# legoCrawlerArduinoMegaExtension.net
KiCad netlist of a schematic drawn in EAGLE
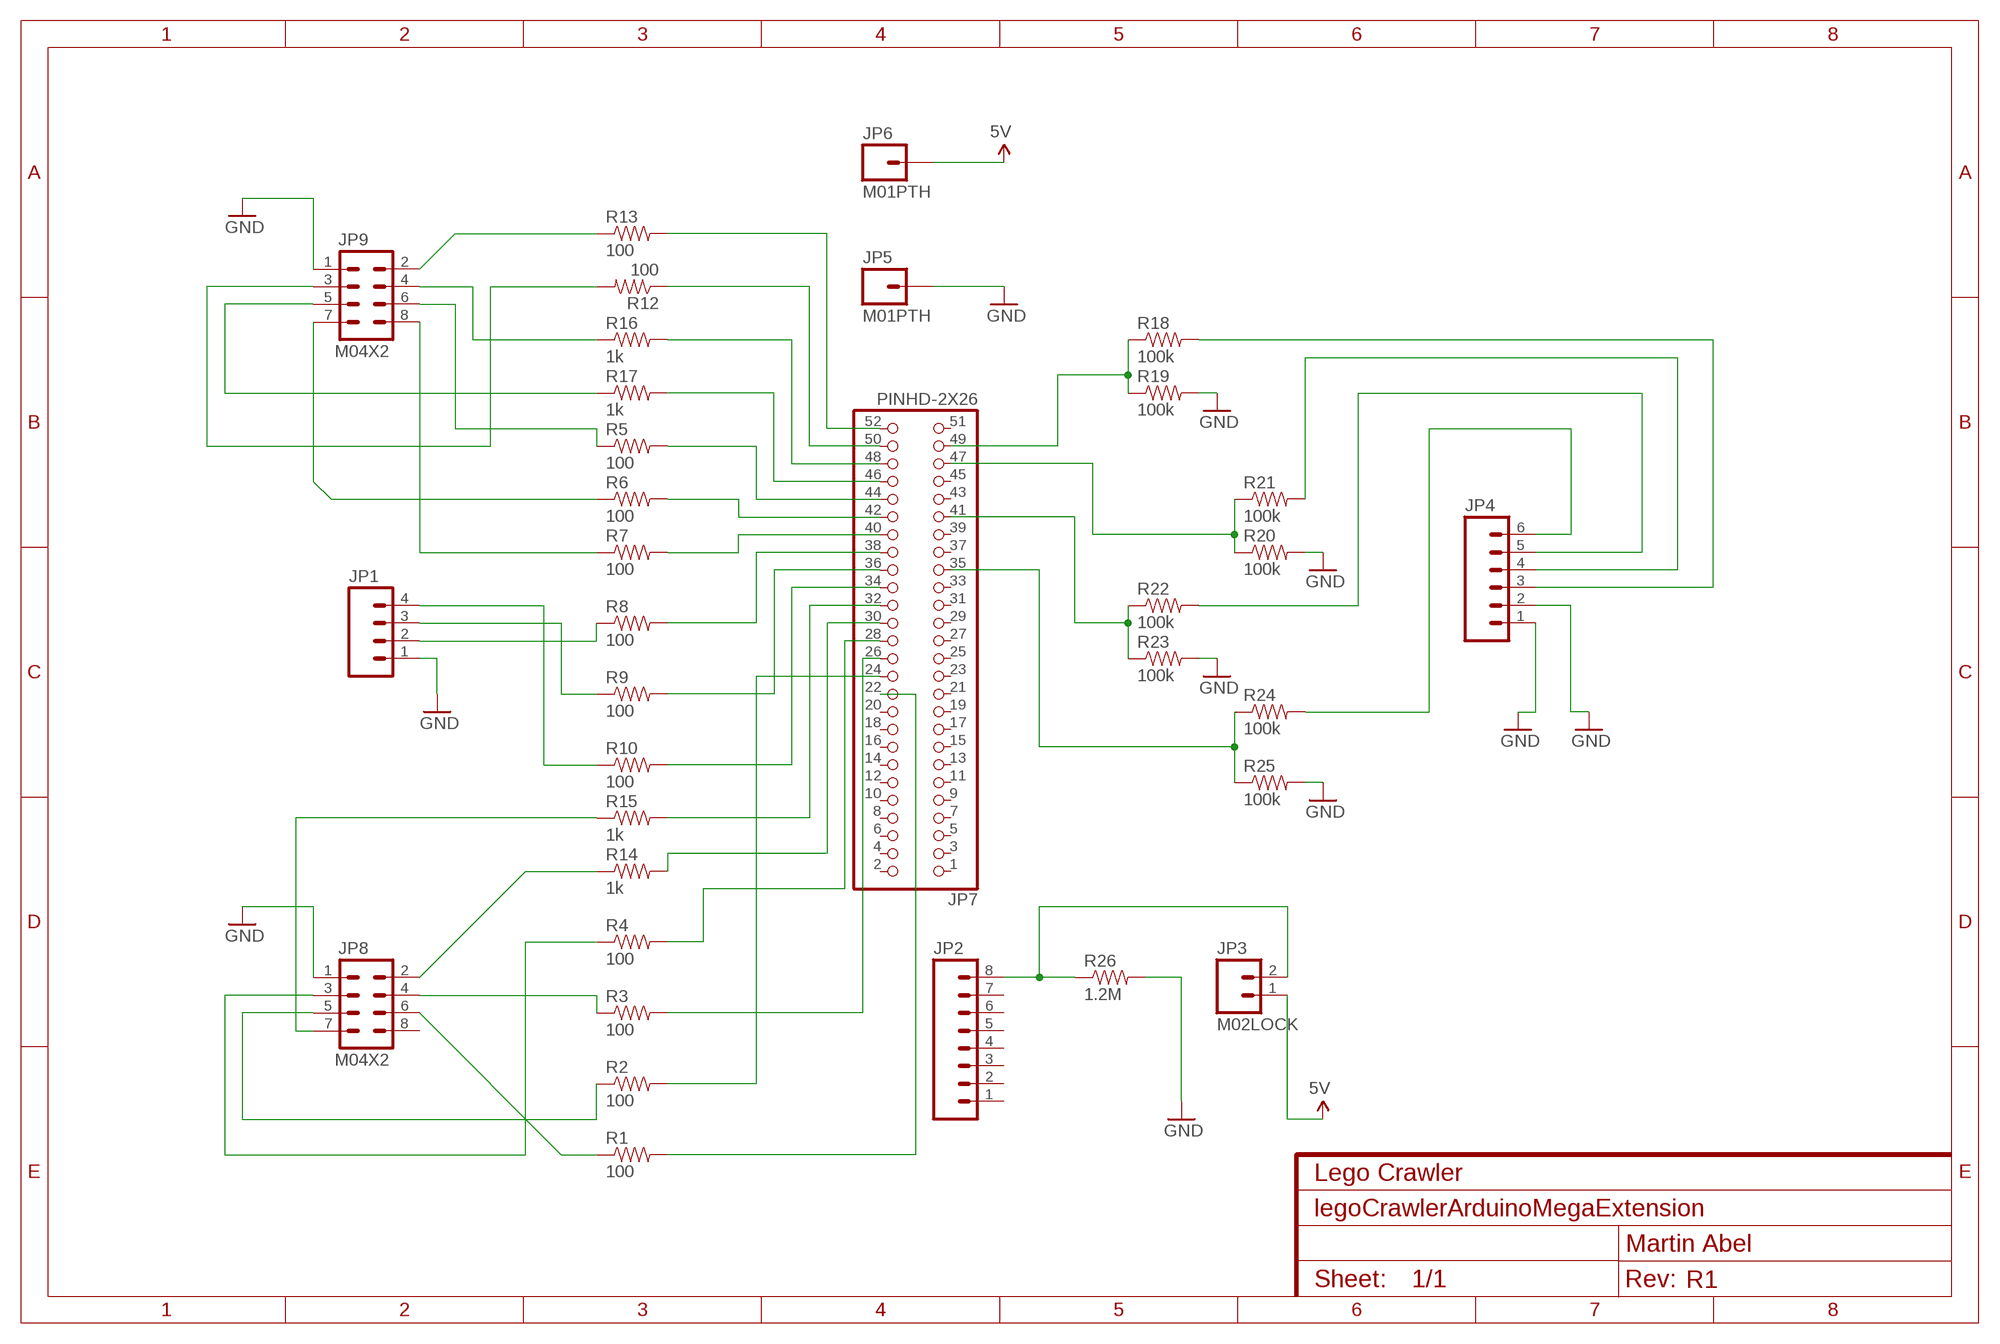
[diagram p0: schematic, sheet 1]

(export (version "E")
  (design (tool "Eeschema 10.0.6"))
  (components
    (comp (ref "JP1")
      (value "M04JST")
      (footprint "eagle-import:1X04-1.5MM_JST")
      (libsource (lib "eagle-import") (part "M04JST"))
    )
    (comp (ref "JP2")
      (value "M08")
      (footprint "eagle-import:1X08_ROUND")
      (libsource (lib "eagle-import") (part "M08"))
    )
    (comp (ref "JP3")
      (value "M02LOCK")
      (footprint "eagle-import:1X02_LOCK")
      (libsource (lib "eagle-import") (part "M02LOCK"))
    )
    (comp (ref "JP4")
      (value "M06LOCK")
      (footprint "eagle-import:1X06_LOCK")
      (libsource (lib "eagle-import") (part "M06LOCK"))
    )
    (comp (ref "JP5")
      (value "M01PTH")
      (footprint "eagle-import:1X01")
      (libsource (lib "eagle-import") (part "M01PTH"))
    )
    (comp (ref "JP6")
      (value "M01PTH")
      (footprint "eagle-import:1X01")
      (libsource (lib "eagle-import") (part "M01PTH"))
    )
    (comp (ref "JP7")
      (value "PINHD-2X26")
      (footprint "eagle-import:2X26")
      (libsource (lib "eagle-import") (part "PINHD-2X26"))
    )
    (comp (ref "JP8")
      (value "M04X2")
      (footprint "eagle-import:2X4")
      (libsource (lib "eagle-import") (part "M04X2"))
    )
    (comp (ref "JP9")
      (value "M04X2")
      (footprint "eagle-import:2X4")
      (libsource (lib "eagle-import") (part "M04X2"))
    )
    (comp (ref "R1")
      (value "100")
      (footprint "eagle-import:AXIAL-0.3")
      (libsource (lib "eagle-import") (part "10OHM-1/4W-5%(PTH)"))
    )
    (comp (ref "R2")
      (value "100")
      (footprint "eagle-import:AXIAL-0.3")
      (libsource (lib "eagle-import") (part "10OHM-1/4W-5%(PTH)"))
    )
    (comp (ref "R3")
      (value "100")
      (footprint "eagle-import:AXIAL-0.3")
      (libsource (lib "eagle-import") (part "10OHM-1/4W-5%(PTH)"))
    )
    (comp (ref "R4")
      (value "100")
      (footprint "eagle-import:AXIAL-0.3")
      (libsource (lib "eagle-import") (part "10OHM-1/4W-5%(PTH)"))
    )
    (comp (ref "R5")
      (value "100")
      (footprint "eagle-import:AXIAL-0.3")
      (libsource (lib "eagle-import") (part "10OHM-1/4W-5%(PTH)"))
    )
    (comp (ref "R6")
      (value "100")
      (footprint "eagle-import:AXIAL-0.3")
      (libsource (lib "eagle-import") (part "10OHM-1/4W-5%(PTH)"))
    )
    (comp (ref "R7")
      (value "100")
      (footprint "eagle-import:AXIAL-0.3")
      (libsource (lib "eagle-import") (part "10OHM-1/4W-5%(PTH)"))
    )
    (comp (ref "R8")
      (value "100")
      (footprint "eagle-import:AXIAL-0.3")
      (libsource (lib "eagle-import") (part "10OHM-1/4W-5%(PTH)"))
    )
    (comp (ref "R9")
      (value "100")
      (footprint "eagle-import:AXIAL-0.3")
      (libsource (lib "eagle-import") (part "10OHM-1/4W-5%(PTH)"))
    )
    (comp (ref "R10")
      (value "100")
      (footprint "eagle-import:AXIAL-0.3")
      (libsource (lib "eagle-import") (part "10OHM-1/4W-5%(PTH)"))
    )
    (comp (ref "R12")
      (value "100")
      (footprint "eagle-import:AXIAL-0.3")
      (libsource (lib "eagle-import") (part "10OHM-1/4W-5%(PTH)"))
    )
    (comp (ref "R13")
      (value "100")
      (footprint "eagle-import:AXIAL-0.3")
      (libsource (lib "eagle-import") (part "10OHM-1/4W-5%(PTH)"))
    )
    (comp (ref "R14")
      (value "1k")
      (footprint "eagle-import:AXIAL-0.3")
      (libsource (lib "eagle-import") (part "1KOHM-1/4W-5%(PTH)"))
    )
    (comp (ref "R15")
      (value "1k")
      (footprint "eagle-import:AXIAL-0.3")
      (libsource (lib "eagle-import") (part "1KOHM-1/4W-5%(PTH)"))
    )
    (comp (ref "R16")
      (value "1k")
      (footprint "eagle-import:AXIAL-0.3")
      (libsource (lib "eagle-import") (part "1KOHM-1/4W-5%(PTH)"))
    )
    (comp (ref "R17")
      (value "1k")
      (footprint "eagle-import:AXIAL-0.3")
      (libsource (lib "eagle-import") (part "1KOHM-1/4W-5%(PTH)"))
    )
    (comp (ref "R18")
      (value "100k")
      (footprint "eagle-import:AXIAL-0.3")
      (libsource (lib "eagle-import") (part "100KOHM-1/4W-5%(PTH)"))
    )
    (comp (ref "R19")
      (value "100k")
      (footprint "eagle-import:AXIAL-0.3")
      (libsource (lib "eagle-import") (part "100KOHM-1/4W-5%(PTH)"))
    )
    (comp (ref "R20")
      (value "100k")
      (footprint "eagle-import:AXIAL-0.3")
      (libsource (lib "eagle-import") (part "100KOHM-1/4W-5%(PTH)"))
    )
    (comp (ref "R21")
      (value "100k")
      (footprint "eagle-import:AXIAL-0.3")
      (libsource (lib "eagle-import") (part "100KOHM-1/4W-5%(PTH)"))
    )
    (comp (ref "R22")
      (value "100k")
      (footprint "eagle-import:AXIAL-0.3")
      (libsource (lib "eagle-import") (part "100KOHM-1/4W-5%(PTH)"))
    )
    (comp (ref "R23")
      (value "100k")
      (footprint "eagle-import:AXIAL-0.3")
      (libsource (lib "eagle-import") (part "100KOHM-1/4W-5%(PTH)"))
    )
    (comp (ref "R24")
      (value "100k")
      (footprint "eagle-import:AXIAL-0.3")
      (libsource (lib "eagle-import") (part "100KOHM-1/4W-5%(PTH)"))
    )
    (comp (ref "R25")
      (value "100k")
      (footprint "eagle-import:AXIAL-0.3")
      (libsource (lib "eagle-import") (part "100KOHM-1/4W-5%(PTH)"))
    )
    (comp (ref "R26")
      (value "1.2M")
      (footprint "eagle-import:0603-RES")
      (libsource (lib "eagle-import") (part "1.2MOHMS-1/10W-1%(0603)"))
    )
  )
  (nets
    (net (code "1") (name "5V") (class "Default")
      (node (ref "JP3") (pin "1") (pinfunction "1_1") (pintype "passive"))
      (node (ref "JP6") (pin "1") (pinfunction "1_1") (pintype "passive"))
    )
    (net (code "2") (name "GND") (class "Default")
      (node (ref "JP1") (pin "1") (pinfunction "1_1") (pintype "passive"))
      (node (ref "JP4") (pin "1") (pinfunction "1_1") (pintype "passive"))
      (node (ref "JP4") (pin "2") (pinfunction "2_2") (pintype "passive"))
      (node (ref "JP5") (pin "1") (pinfunction "1_1") (pintype "passive"))
      (node (ref "JP8") (pin "1") (pinfunction "1_1") (pintype "passive"))
      (node (ref "JP9") (pin "1") (pinfunction "1_1") (pintype "passive"))
      (node (ref "R19") (pin "P$2") (pinfunction "2_P$2") (pintype "passive"))
      (node (ref "R20") (pin "P$2") (pinfunction "2_P$2") (pintype "passive"))
      (node (ref "R23") (pin "P$2") (pinfunction "2_P$2") (pintype "passive"))
      (node (ref "R25") (pin "P$2") (pinfunction "2_P$2") (pintype "passive"))
      (node (ref "R26") (pin "2") (pinfunction "2_2") (pintype "passive"))
    )
    (net (code "3") (name "Net-(JP2-Pad8)") (class "Default")
      (node (ref "JP2") (pin "8") (pinfunction "8_8") (pintype "passive"))
      (node (ref "JP3") (pin "2") (pinfunction "2_2") (pintype "passive"))
      (node (ref "R26") (pin "1") (pinfunction "1_1") (pintype "passive"))
    )
    (net (code "4") (name "Net-(R1-1)") (class "Default")
      (node (ref "JP8") (pin "6") (pinfunction "6_6") (pintype "passive"))
      (node (ref "R1") (pin "P$1") (pinfunction "1_P$1") (pintype "passive"))
    )
    (net (code "5") (name "Net-(R1-2)") (class "Default")
      (node (ref "JP7") (pin "22") (pinfunction "22_22") (pintype "passive"))
      (node (ref "R1") (pin "P$2") (pinfunction "2_P$2") (pintype "passive"))
    )
    (net (code "6") (name "Net-(R2-1)") (class "Default")
      (node (ref "JP8") (pin "5") (pinfunction "5_5") (pintype "passive"))
      (node (ref "R2") (pin "P$1") (pinfunction "1_P$1") (pintype "passive"))
    )
    (net (code "7") (name "Net-(R2-2)") (class "Default")
      (node (ref "JP7") (pin "24") (pinfunction "24_24") (pintype "passive"))
      (node (ref "R2") (pin "P$2") (pinfunction "2_P$2") (pintype "passive"))
    )
    (net (code "8") (name "Net-(R3-1)") (class "Default")
      (node (ref "JP8") (pin "4") (pinfunction "4_4") (pintype "passive"))
      (node (ref "R3") (pin "P$1") (pinfunction "1_P$1") (pintype "passive"))
    )
    (net (code "9") (name "Net-(R3-2)") (class "Default")
      (node (ref "JP7") (pin "26") (pinfunction "26_26") (pintype "passive"))
      (node (ref "R3") (pin "P$2") (pinfunction "2_P$2") (pintype "passive"))
    )
    (net (code "10") (name "Net-(R4-1)") (class "Default")
      (node (ref "JP8") (pin "3") (pinfunction "3_3") (pintype "passive"))
      (node (ref "R4") (pin "P$1") (pinfunction "1_P$1") (pintype "passive"))
    )
    (net (code "11") (name "Net-(R4-2)") (class "Default")
      (node (ref "JP7") (pin "28") (pinfunction "28_28") (pintype "passive"))
      (node (ref "R4") (pin "P$2") (pinfunction "2_P$2") (pintype "passive"))
    )
    (net (code "12") (name "Net-(R5-1)") (class "Default")
      (node (ref "JP9") (pin "6") (pinfunction "6_6") (pintype "passive"))
      (node (ref "R5") (pin "P$1") (pinfunction "1_P$1") (pintype "passive"))
    )
    (net (code "13") (name "Net-(R5-2)") (class "Default")
      (node (ref "JP7") (pin "44") (pinfunction "44_44") (pintype "passive"))
      (node (ref "R5") (pin "P$2") (pinfunction "2_P$2") (pintype "passive"))
    )
    (net (code "14") (name "Net-(R6-1)") (class "Default")
      (node (ref "JP9") (pin "7") (pinfunction "7_7") (pintype "passive"))
      (node (ref "R6") (pin "P$1") (pinfunction "1_P$1") (pintype "passive"))
    )
    (net (code "15") (name "Net-(R6-2)") (class "Default")
      (node (ref "JP7") (pin "42") (pinfunction "42_42") (pintype "passive"))
      (node (ref "R6") (pin "P$2") (pinfunction "2_P$2") (pintype "passive"))
    )
    (net (code "16") (name "Net-(R7-1)") (class "Default")
      (node (ref "JP9") (pin "8") (pinfunction "8_8") (pintype "passive"))
      (node (ref "R7") (pin "P$1") (pinfunction "1_P$1") (pintype "passive"))
    )
    (net (code "17") (name "Net-(R7-2)") (class "Default")
      (node (ref "JP7") (pin "40") (pinfunction "40_40") (pintype "passive"))
      (node (ref "R7") (pin "P$2") (pinfunction "2_P$2") (pintype "passive"))
    )
    (net (code "18") (name "Net-(R8-1)") (class "Default")
      (node (ref "JP1") (pin "2") (pinfunction "2_2") (pintype "passive"))
      (node (ref "R8") (pin "P$1") (pinfunction "1_P$1") (pintype "passive"))
    )
    (net (code "19") (name "Net-(R8-2)") (class "Default")
      (node (ref "JP7") (pin "38") (pinfunction "38_38") (pintype "passive"))
      (node (ref "R8") (pin "P$2") (pinfunction "2_P$2") (pintype "passive"))
    )
    (net (code "20") (name "Net-(R9-1)") (class "Default")
      (node (ref "JP1") (pin "3") (pinfunction "3_3") (pintype "passive"))
      (node (ref "R9") (pin "P$1") (pinfunction "1_P$1") (pintype "passive"))
    )
    (net (code "21") (name "Net-(R9-2)") (class "Default")
      (node (ref "JP7") (pin "36") (pinfunction "36_36") (pintype "passive"))
      (node (ref "R9") (pin "P$2") (pinfunction "2_P$2") (pintype "passive"))
    )
    (net (code "22") (name "Net-(R10-1)") (class "Default")
      (node (ref "JP1") (pin "4") (pinfunction "4_4") (pintype "passive"))
      (node (ref "R10") (pin "P$1") (pinfunction "1_P$1") (pintype "passive"))
    )
    (net (code "23") (name "Net-(R10-2)") (class "Default")
      (node (ref "JP7") (pin "34") (pinfunction "34_34") (pintype "passive"))
      (node (ref "R10") (pin "P$2") (pinfunction "2_P$2") (pintype "passive"))
    )
    (net (code "24") (name "Net-(R12-1)") (class "Default")
      (node (ref "JP7") (pin "50") (pinfunction "50_50") (pintype "passive"))
      (node (ref "R12") (pin "P$1") (pinfunction "1_P$1") (pintype "passive"))
    )
    (net (code "25") (name "Net-(R12-2)") (class "Default")
      (node (ref "JP9") (pin "3") (pinfunction "3_3") (pintype "passive"))
      (node (ref "R12") (pin "P$2") (pinfunction "2_P$2") (pintype "passive"))
    )
    (net (code "26") (name "Net-(R13-1)") (class "Default")
      (node (ref "JP9") (pin "2") (pinfunction "2_2") (pintype "passive"))
      (node (ref "R13") (pin "P$1") (pinfunction "1_P$1") (pintype "passive"))
    )
    (net (code "27") (name "Net-(R13-2)") (class "Default")
      (node (ref "JP7") (pin "52") (pinfunction "52_52") (pintype "passive"))
      (node (ref "R13") (pin "P$2") (pinfunction "2_P$2") (pintype "passive"))
    )
    (net (code "28") (name "Net-(R14-1)") (class "Default")
      (node (ref "JP8") (pin "2") (pinfunction "2_2") (pintype "passive"))
      (node (ref "R14") (pin "P$1") (pinfunction "1_P$1") (pintype "passive"))
    )
    (net (code "29") (name "Net-(R14-2)") (class "Default")
      (node (ref "JP7") (pin "30") (pinfunction "30_30") (pintype "passive"))
      (node (ref "R14") (pin "P$2") (pinfunction "2_P$2") (pintype "passive"))
    )
    (net (code "30") (name "Net-(R15-1)") (class "Default")
      (node (ref "JP8") (pin "7") (pinfunction "7_7") (pintype "passive"))
      (node (ref "R15") (pin "P$1") (pinfunction "1_P$1") (pintype "passive"))
    )
    (net (code "31") (name "Net-(R15-2)") (class "Default")
      (node (ref "JP7") (pin "32") (pinfunction "32_32") (pintype "passive"))
      (node (ref "R15") (pin "P$2") (pinfunction "2_P$2") (pintype "passive"))
    )
    (net (code "32") (name "Net-(R16-1)") (class "Default")
      (node (ref "JP9") (pin "4") (pinfunction "4_4") (pintype "passive"))
      (node (ref "R16") (pin "P$1") (pinfunction "1_P$1") (pintype "passive"))
    )
    (net (code "33") (name "Net-(R16-2)") (class "Default")
      (node (ref "JP7") (pin "48") (pinfunction "48_48") (pintype "passive"))
      (node (ref "R16") (pin "P$2") (pinfunction "2_P$2") (pintype "passive"))
    )
    (net (code "34") (name "Net-(R17-1)") (class "Default")
      (node (ref "JP9") (pin "5") (pinfunction "5_5") (pintype "passive"))
      (node (ref "R17") (pin "P$1") (pinfunction "1_P$1") (pintype "passive"))
    )
    (net (code "35") (name "Net-(R17-2)") (class "Default")
      (node (ref "JP7") (pin "46") (pinfunction "46_46") (pintype "passive"))
      (node (ref "R17") (pin "P$2") (pinfunction "2_P$2") (pintype "passive"))
    )
    (net (code "36") (name "Net-(R18-1)") (class "Default")
      (node (ref "JP7") (pin "49") (pinfunction "49_49") (pintype "passive"))
      (node (ref "R18") (pin "P$1") (pinfunction "1_P$1") (pintype "passive"))
      (node (ref "R19") (pin "P$1") (pinfunction "1_P$1") (pintype "passive"))
    )
    (net (code "37") (name "Net-(R18-2)") (class "Default")
      (node (ref "JP4") (pin "3") (pinfunction "3_3") (pintype "passive"))
      (node (ref "R18") (pin "P$2") (pinfunction "2_P$2") (pintype "passive"))
    )
    (net (code "38") (name "Net-(R20-1)") (class "Default")
      (node (ref "JP7") (pin "47") (pinfunction "47_47") (pintype "passive"))
      (node (ref "R20") (pin "P$1") (pinfunction "1_P$1") (pintype "passive"))
      (node (ref "R21") (pin "P$1") (pinfunction "1_P$1") (pintype "passive"))
    )
    (net (code "39") (name "Net-(R21-2)") (class "Default")
      (node (ref "JP4") (pin "4") (pinfunction "4_4") (pintype "passive"))
      (node (ref "R21") (pin "P$2") (pinfunction "2_P$2") (pintype "passive"))
    )
    (net (code "40") (name "Net-(R22-1)") (class "Default")
      (node (ref "JP7") (pin "41") (pinfunction "41_41") (pintype "passive"))
      (node (ref "R22") (pin "P$1") (pinfunction "1_P$1") (pintype "passive"))
      (node (ref "R23") (pin "P$1") (pinfunction "1_P$1") (pintype "passive"))
    )
    (net (code "41") (name "Net-(R22-2)") (class "Default")
      (node (ref "JP4") (pin "5") (pinfunction "5_5") (pintype "passive"))
      (node (ref "R22") (pin "P$2") (pinfunction "2_P$2") (pintype "passive"))
    )
    (net (code "42") (name "Net-(R24-1)") (class "Default")
      (node (ref "JP7") (pin "35") (pinfunction "35_35") (pintype "passive"))
      (node (ref "R24") (pin "P$1") (pinfunction "1_P$1") (pintype "passive"))
      (node (ref "R25") (pin "P$1") (pinfunction "1_P$1") (pintype "passive"))
    )
    (net (code "43") (name "Net-(R24-2)") (class "Default")
      (node (ref "JP4") (pin "6") (pinfunction "6_6") (pintype "passive"))
      (node (ref "R24") (pin "P$2") (pinfunction "2_P$2") (pintype "passive"))
    )
    (net (code "44") (name "unconnected-(JP2-Pad1)") (class "Default")
      (node (ref "JP2") (pin "1") (pinfunction "1_1") (pintype "passive"))
    )
    (net (code "45") (name "unconnected-(JP2-Pad2)") (class "Default")
      (node (ref "JP2") (pin "2") (pinfunction "2_2") (pintype "passive"))
    )
    (net (code "46") (name "unconnected-(JP2-Pad3)") (class "Default")
      (node (ref "JP2") (pin "3") (pinfunction "3_3") (pintype "passive"))
    )
    (net (code "47") (name "unconnected-(JP2-Pad4)") (class "Default")
      (node (ref "JP2") (pin "4") (pinfunction "4_4") (pintype "passive"))
    )
    (net (code "48") (name "unconnected-(JP2-Pad5)") (class "Default")
      (node (ref "JP2") (pin "5") (pinfunction "5_5") (pintype "passive"))
    )
    (net (code "49") (name "unconnected-(JP2-Pad6)") (class "Default")
      (node (ref "JP2") (pin "6") (pinfunction "6_6") (pintype "passive"))
    )
    (net (code "50") (name "unconnected-(JP2-Pad7)") (class "Default")
      (node (ref "JP2") (pin "7") (pinfunction "7_7") (pintype "passive"))
    )
    (net (code "51") (name "unconnected-(JP7-Pad1)") (class "Default")
      (node (ref "JP7") (pin "1") (pinfunction "1_1") (pintype "passive"))
    )
    (net (code "52") (name "unconnected-(JP7-Pad2)") (class "Default")
      (node (ref "JP7") (pin "2") (pinfunction "2_2") (pintype "passive"))
    )
    (net (code "53") (name "unconnected-(JP7-Pad3)") (class "Default")
      (node (ref "JP7") (pin "3") (pinfunction "3_3") (pintype "passive"))
    )
    (net (code "54") (name "unconnected-(JP7-Pad4)") (class "Default")
      (node (ref "JP7") (pin "4") (pinfunction "4_4") (pintype "passive"))
    )
    (net (code "55") (name "unconnected-(JP7-Pad5)") (class "Default")
      (node (ref "JP7") (pin "5") (pinfunction "5_5") (pintype "passive"))
    )
    (net (code "56") (name "unconnected-(JP7-Pad6)") (class "Default")
      (node (ref "JP7") (pin "6") (pinfunction "6_6") (pintype "passive"))
    )
    (net (code "57") (name "unconnected-(JP7-Pad7)") (class "Default")
      (node (ref "JP7") (pin "7") (pinfunction "7_7") (pintype "passive"))
    )
    (net (code "58") (name "unconnected-(JP7-Pad8)") (class "Default")
      (node (ref "JP7") (pin "8") (pinfunction "8_8") (pintype "passive"))
    )
    (net (code "59") (name "unconnected-(JP7-Pad9)") (class "Default")
      (node (ref "JP7") (pin "9") (pinfunction "9_9") (pintype "passive"))
    )
    (net (code "60") (name "unconnected-(JP7-Pad10)") (class "Default")
      (node (ref "JP7") (pin "10") (pinfunction "10_10") (pintype "passive"))
    )
    (net (code "61") (name "unconnected-(JP7-Pad11)") (class "Default")
      (node (ref "JP7") (pin "11") (pinfunction "11_11") (pintype "passive"))
    )
    (net (code "62") (name "unconnected-(JP7-Pad12)") (class "Default")
      (node (ref "JP7") (pin "12") (pinfunction "12_12") (pintype "passive"))
    )
    (net (code "63") (name "unconnected-(JP7-Pad13)") (class "Default")
      (node (ref "JP7") (pin "13") (pinfunction "13_13") (pintype "passive"))
    )
    (net (code "64") (name "unconnected-(JP7-Pad14)") (class "Default")
      (node (ref "JP7") (pin "14") (pinfunction "14_14") (pintype "passive"))
    )
    (net (code "65") (name "unconnected-(JP7-Pad15)") (class "Default")
      (node (ref "JP7") (pin "15") (pinfunction "15_15") (pintype "passive"))
    )
    (net (code "66") (name "unconnected-(JP7-Pad16)") (class "Default")
      (node (ref "JP7") (pin "16") (pinfunction "16_16") (pintype "passive"))
    )
    (net (code "67") (name "unconnected-(JP7-Pad17)") (class "Default")
      (node (ref "JP7") (pin "17") (pinfunction "17_17") (pintype "passive"))
    )
    (net (code "68") (name "unconnected-(JP7-Pad18)") (class "Default")
      (node (ref "JP7") (pin "18") (pinfunction "18_18") (pintype "passive"))
    )
    (net (code "69") (name "unconnected-(JP7-Pad19)") (class "Default")
      (node (ref "JP7") (pin "19") (pinfunction "19_19") (pintype "passive"))
    )
    (net (code "70") (name "unconnected-(JP7-Pad20)") (class "Default")
      (node (ref "JP7") (pin "20") (pinfunction "20_20") (pintype "passive"))
    )
    (net (code "71") (name "unconnected-(JP7-Pad21)") (class "Default")
      (node (ref "JP7") (pin "21") (pinfunction "21_21") (pintype "passive"))
    )
    (net (code "72") (name "unconnected-(JP7-Pad23)") (class "Default")
      (node (ref "JP7") (pin "23") (pinfunction "23_23") (pintype "passive"))
    )
    (net (code "73") (name "unconnected-(JP7-Pad25)") (class "Default")
      (node (ref "JP7") (pin "25") (pinfunction "25_25") (pintype "passive"))
    )
    (net (code "74") (name "unconnected-(JP7-Pad27)") (class "Default")
      (node (ref "JP7") (pin "27") (pinfunction "27_27") (pintype "passive"))
    )
    (net (code "75") (name "unconnected-(JP7-Pad29)") (class "Default")
      (node (ref "JP7") (pin "29") (pinfunction "29_29") (pintype "passive"))
    )
    (net (code "76") (name "unconnected-(JP7-Pad31)") (class "Default")
      (node (ref "JP7") (pin "31") (pinfunction "31_31") (pintype "passive"))
    )
    (net (code "77") (name "unconnected-(JP7-Pad33)") (class "Default")
      (node (ref "JP7") (pin "33") (pinfunction "33_33") (pintype "passive"))
    )
    (net (code "78") (name "unconnected-(JP7-Pad37)") (class "Default")
      (node (ref "JP7") (pin "37") (pinfunction "37_37") (pintype "passive"))
    )
    (net (code "79") (name "unconnected-(JP7-Pad39)") (class "Default")
      (node (ref "JP7") (pin "39") (pinfunction "39_39") (pintype "passive"))
    )
    (net (code "80") (name "unconnected-(JP7-Pad43)") (class "Default")
      (node (ref "JP7") (pin "43") (pinfunction "43_43") (pintype "passive"))
    )
    (net (code "81") (name "unconnected-(JP7-Pad45)") (class "Default")
      (node (ref "JP7") (pin "45") (pinfunction "45_45") (pintype "passive"))
    )
    (net (code "82") (name "unconnected-(JP7-Pad51)") (class "Default")
      (node (ref "JP7") (pin "51") (pinfunction "51_51") (pintype "passive"))
    )
    (net (code "83") (name "unconnected-(JP8-Pad8)") (class "Default")
      (node (ref "JP8") (pin "8") (pinfunction "8_8") (pintype "passive"))
    )
  )
)
